# Scheda_motori_a4988.net
KiCad netlist of a schematic drawn in EAGLE
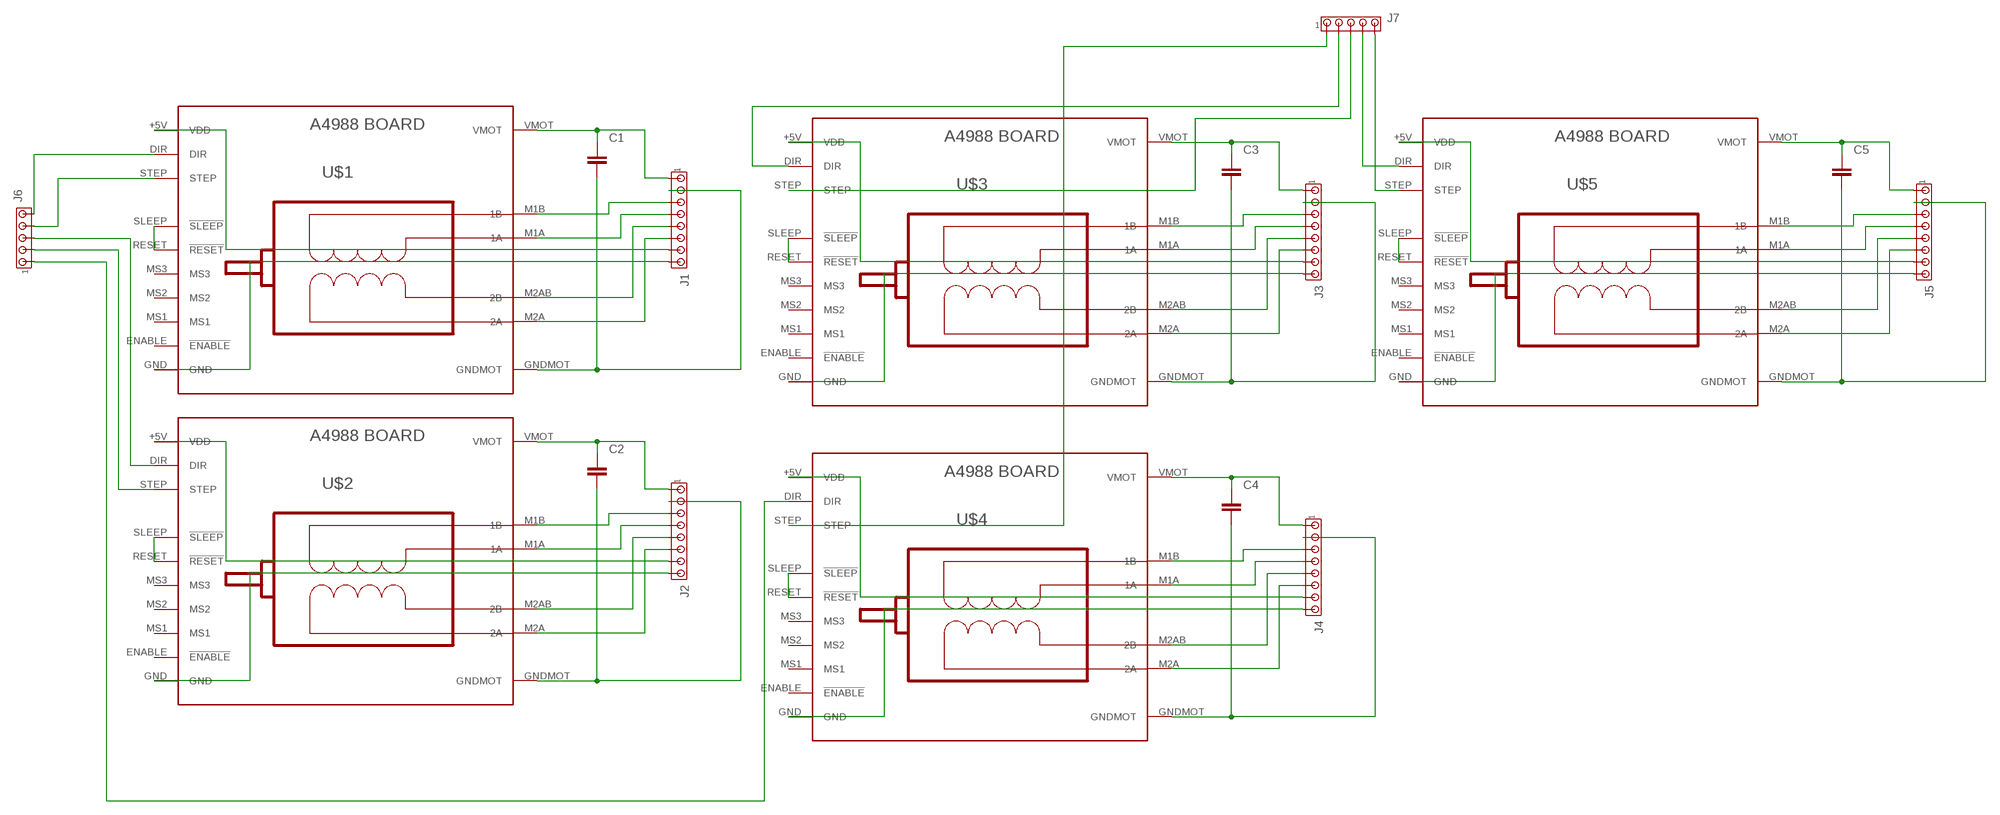
[diagram p0: schematic, sheet 1]

(export (version "E")
  (design (tool "Eeschema 10.0.6"))
  (components
    (comp (ref "C1")
      (value "C_RADIAL-12.5MM-DIA")
      (footprint "eagle-import:CAPRD550W60D1025H1250B")
      (libsource (lib "eagle-import") (part "CRADIAL-12.5MM-DIA_"))
    )
    (comp (ref "C2")
      (value "C_RADIAL-12.5MM-DIA")
      (footprint "eagle-import:CAPRD550W60D1025H1250B")
      (libsource (lib "eagle-import") (part "CRADIAL-12.5MM-DIA_"))
    )
    (comp (ref "C3")
      (value "C_RADIAL-12.5MM-DIA")
      (footprint "eagle-import:CAPRD550W60D1025H1250B")
      (libsource (lib "eagle-import") (part "CRADIAL-12.5MM-DIA_"))
    )
    (comp (ref "C4")
      (value "C_RADIAL-12.5MM-DIA")
      (footprint "eagle-import:CAPRD550W60D1025H1250B")
      (libsource (lib "eagle-import") (part "CRADIAL-12.5MM-DIA_"))
    )
    (comp (ref "C5")
      (value "C_RADIAL-12.5MM-DIA")
      (footprint "eagle-import:CAPRD550W60D1025H1250B")
      (libsource (lib "eagle-import") (part "CRADIAL-12.5MM-DIA_"))
    )
    (comp (ref "J1")
      (value "MTA08-100")
      (footprint "eagle-import:10X08MTA")
      (libsource (lib "eagle-import") (part "MTA08-100"))
    )
    (comp (ref "J2")
      (value "MTA08-100")
      (footprint "eagle-import:10X08MTA")
      (libsource (lib "eagle-import") (part "MTA08-100"))
    )
    (comp (ref "J3")
      (value "MTA08-100")
      (footprint "eagle-import:10X08MTA")
      (libsource (lib "eagle-import") (part "MTA08-100"))
    )
    (comp (ref "J4")
      (value "MTA08-100")
      (footprint "eagle-import:10X08MTA")
      (libsource (lib "eagle-import") (part "MTA08-100"))
    )
    (comp (ref "J5")
      (value "MTA08-100")
      (footprint "eagle-import:10X08MTA")
      (libsource (lib "eagle-import") (part "MTA08-100"))
    )
    (comp (ref "J6")
      (value "MTA05-156")
      (footprint "eagle-import:1X5MTA")
      (libsource (lib "eagle-import") (part "MTA05-156"))
    )
    (comp (ref "J7")
      (value "MTA05-156")
      (footprint "eagle-import:1X5MTA")
      (libsource (lib "eagle-import") (part "MTA05-156"))
    )
    (comp (ref "U$1")
      (value "BOARD_A4988")
      (footprint "eagle-import:BOARD_A4988")
      (libsource (lib "eagle-import") (part "BOARD_A4988"))
    )
    (comp (ref "U$2")
      (value "BOARD_A4988")
      (footprint "eagle-import:BOARD_A4988")
      (libsource (lib "eagle-import") (part "BOARD_A4988"))
    )
    (comp (ref "U$3")
      (value "BOARD_A4988")
      (footprint "eagle-import:BOARD_A4988")
      (libsource (lib "eagle-import") (part "BOARD_A4988"))
    )
    (comp (ref "U$4")
      (value "BOARD_A4988")
      (footprint "eagle-import:BOARD_A4988")
      (libsource (lib "eagle-import") (part "BOARD_A4988"))
    )
    (comp (ref "U$5")
      (value "BOARD_A4988")
      (footprint "eagle-import:BOARD_A4988")
      (libsource (lib "eagle-import") (part "BOARD_A4988"))
    )
  )
  (nets
    (net (code "1") (name "Net-(C1-Pad1)") (class "Default")
      (node (ref "C1") (pin "1") (pinfunction "1_1") (pintype "passive"))
      (node (ref "J1") (pin "1") (pinfunction "1_1") (pintype "passive"))
      (node (ref "U$1") (pin "VMOT") (pinfunction "VMOT_VMOT") (pintype "power_in"))
    )
    (net (code "2") (name "Net-(C1-Pad2)") (class "Default")
      (node (ref "C1") (pin "2") (pinfunction "2_2") (pintype "passive"))
      (node (ref "J1") (pin "2") (pinfunction "2_2") (pintype "passive"))
      (node (ref "U$1") (pin "GNDMOT") (pinfunction "GNDMOT_GNDMOT") (pintype "power_in"))
    )
    (net (code "3") (name "Net-(C2-Pad1)") (class "Default")
      (node (ref "C2") (pin "1") (pinfunction "1_1") (pintype "passive"))
      (node (ref "J2") (pin "1") (pinfunction "1_1") (pintype "passive"))
      (node (ref "U$2") (pin "VMOT") (pinfunction "VMOT_VMOT") (pintype "power_in"))
    )
    (net (code "4") (name "Net-(C2-Pad2)") (class "Default")
      (node (ref "C2") (pin "2") (pinfunction "2_2") (pintype "passive"))
      (node (ref "J2") (pin "2") (pinfunction "2_2") (pintype "passive"))
      (node (ref "U$2") (pin "GNDMOT") (pinfunction "GNDMOT_GNDMOT") (pintype "power_in"))
    )
    (net (code "5") (name "Net-(C3-Pad1)") (class "Default")
      (node (ref "C3") (pin "1") (pinfunction "1_1") (pintype "passive"))
      (node (ref "J3") (pin "1") (pinfunction "1_1") (pintype "passive"))
      (node (ref "U$3") (pin "VMOT") (pinfunction "VMOT_VMOT") (pintype "power_in"))
    )
    (net (code "6") (name "Net-(C3-Pad2)") (class "Default")
      (node (ref "C3") (pin "2") (pinfunction "2_2") (pintype "passive"))
      (node (ref "J3") (pin "2") (pinfunction "2_2") (pintype "passive"))
      (node (ref "U$3") (pin "GNDMOT") (pinfunction "GNDMOT_GNDMOT") (pintype "power_in"))
    )
    (net (code "7") (name "Net-(C4-Pad1)") (class "Default")
      (node (ref "C4") (pin "1") (pinfunction "1_1") (pintype "passive"))
      (node (ref "J4") (pin "1") (pinfunction "1_1") (pintype "passive"))
      (node (ref "U$4") (pin "VMOT") (pinfunction "VMOT_VMOT") (pintype "power_in"))
    )
    (net (code "8") (name "Net-(C4-Pad2)") (class "Default")
      (node (ref "C4") (pin "2") (pinfunction "2_2") (pintype "passive"))
      (node (ref "J4") (pin "2") (pinfunction "2_2") (pintype "passive"))
      (node (ref "U$4") (pin "GNDMOT") (pinfunction "GNDMOT_GNDMOT") (pintype "power_in"))
    )
    (net (code "9") (name "Net-(C5-Pad1)") (class "Default")
      (node (ref "C5") (pin "1") (pinfunction "1_1") (pintype "passive"))
      (node (ref "J5") (pin "1") (pinfunction "1_1") (pintype "passive"))
      (node (ref "U$5") (pin "VMOT") (pinfunction "VMOT_VMOT") (pintype "power_in"))
    )
    (net (code "10") (name "Net-(C5-Pad2)") (class "Default")
      (node (ref "C5") (pin "2") (pinfunction "2_2") (pintype "passive"))
      (node (ref "J5") (pin "2") (pinfunction "2_2") (pintype "passive"))
      (node (ref "U$5") (pin "GNDMOT") (pinfunction "GNDMOT_GNDMOT") (pintype "power_in"))
    )
    (net (code "11") (name "Net-(J1-Pad8)") (class "Default")
      (node (ref "J1") (pin "8") (pinfunction "8_8") (pintype "passive"))
      (node (ref "U$1") (pin "GND") (pinfunction "GND_GND") (pintype "power_in"))
    )
    (net (code "12") (name "Net-(J2-Pad8)") (class "Default")
      (node (ref "J2") (pin "8") (pinfunction "8_8") (pintype "passive"))
      (node (ref "U$2") (pin "GND") (pinfunction "GND_GND") (pintype "power_in"))
    )
    (net (code "13") (name "Net-(J3-Pad8)") (class "Default")
      (node (ref "J3") (pin "8") (pinfunction "8_8") (pintype "passive"))
      (node (ref "U$3") (pin "GND") (pinfunction "GND_GND") (pintype "power_in"))
    )
    (net (code "14") (name "Net-(J4-Pad8)") (class "Default")
      (node (ref "J4") (pin "8") (pinfunction "8_8") (pintype "passive"))
      (node (ref "U$4") (pin "GND") (pinfunction "GND_GND") (pintype "power_in"))
    )
    (net (code "15") (name "Net-(J5-Pad8)") (class "Default")
      (node (ref "J5") (pin "8") (pinfunction "8_8") (pintype "passive"))
      (node (ref "U$5") (pin "GND") (pinfunction "GND_GND") (pintype "power_in"))
    )
    (net (code "16") (name "Net-(J6-Pad1)") (class "Default")
      (node (ref "J6") (pin "1") (pinfunction "1_1") (pintype "passive"))
      (node (ref "U$4") (pin "DIR") (pinfunction "DIR_DIR") (pintype "input"))
    )
    (net (code "17") (name "Net-(J6-Pad2)") (class "Default")
      (node (ref "J6") (pin "2") (pinfunction "2_2") (pintype "passive"))
      (node (ref "U$2") (pin "STEP") (pinfunction "STEP_STEP") (pintype "input"))
    )
    (net (code "18") (name "Net-(J6-Pad3)") (class "Default")
      (node (ref "J6") (pin "3") (pinfunction "3_3") (pintype "passive"))
      (node (ref "U$2") (pin "DIR") (pinfunction "DIR_DIR") (pintype "input"))
    )
    (net (code "19") (name "Net-(J6-Pad4)") (class "Default")
      (node (ref "J6") (pin "4") (pinfunction "4_4") (pintype "passive"))
      (node (ref "U$1") (pin "STEP") (pinfunction "STEP_STEP") (pintype "input"))
    )
    (net (code "20") (name "Net-(J6-Pad5)") (class "Default")
      (node (ref "J6") (pin "5") (pinfunction "5_5") (pintype "passive"))
      (node (ref "U$1") (pin "DIR") (pinfunction "DIR_DIR") (pintype "input"))
    )
    (net (code "21") (name "Net-(J7-Pad1)") (class "Default")
      (node (ref "J7") (pin "1") (pinfunction "1_1") (pintype "passive"))
      (node (ref "U$4") (pin "STEP") (pinfunction "STEP_STEP") (pintype "input"))
    )
    (net (code "22") (name "Net-(J7-Pad2)") (class "Default")
      (node (ref "J7") (pin "2") (pinfunction "2_2") (pintype "passive"))
      (node (ref "U$3") (pin "DIR") (pinfunction "DIR_DIR") (pintype "input"))
    )
    (net (code "23") (name "Net-(J7-Pad3)") (class "Default")
      (node (ref "J7") (pin "3") (pinfunction "3_3") (pintype "passive"))
      (node (ref "U$3") (pin "STEP") (pinfunction "STEP_STEP") (pintype "input"))
    )
    (net (code "24") (name "Net-(J7-Pad4)") (class "Default")
      (node (ref "J7") (pin "4") (pinfunction "4_4") (pintype "passive"))
      (node (ref "U$5") (pin "DIR") (pinfunction "DIR_DIR") (pintype "input"))
    )
    (net (code "25") (name "Net-(J7-Pad5)") (class "Default")
      (node (ref "J7") (pin "5") (pinfunction "5_5") (pintype "passive"))
      (node (ref "U$5") (pin "STEP") (pinfunction "STEP_STEP") (pintype "input"))
    )
    (net (code "26") (name "Net-(U$1-1A)") (class "Default")
      (node (ref "J1") (pin "4") (pinfunction "4_4") (pintype "passive"))
      (node (ref "U$1") (pin "M1A") (pinfunction "1A_M1A") (pintype "output"))
    )
    (net (code "27") (name "Net-(U$1-1B)") (class "Default")
      (node (ref "J1") (pin "3") (pinfunction "3_3") (pintype "passive"))
      (node (ref "U$1") (pin "M1B") (pinfunction "1B_M1B") (pintype "output"))
    )
    (net (code "28") (name "Net-(U$1-2A)") (class "Default")
      (node (ref "J1") (pin "6") (pinfunction "6_6") (pintype "passive"))
      (node (ref "U$1") (pin "M2A") (pinfunction "2A_M2A") (pintype "output"))
    )
    (net (code "29") (name "Net-(U$1-2B)") (class "Default")
      (node (ref "J1") (pin "5") (pinfunction "5_5") (pintype "passive"))
      (node (ref "U$1") (pin "M2AB") (pinfunction "2B_M2AB") (pintype "output"))
    )
    (net (code "30") (name "Net-(U$1-VDD)") (class "Default")
      (node (ref "J1") (pin "7") (pinfunction "7_7") (pintype "passive"))
      (node (ref "U$1") (pin "+5V") (pinfunction "VDD_+5V") (pintype "power_in"))
    )
    (net (code "31") (name "Net-(U$1-~{RESET})") (class "Default")
      (node (ref "U$1") (pin "RESET") (pinfunction "~{RESET}_RESET") (pintype "input"))
      (node (ref "U$1") (pin "SLEEP") (pinfunction "~{SLEEP}_SLEEP") (pintype "input"))
    )
    (net (code "32") (name "Net-(U$2-1A)") (class "Default")
      (node (ref "J2") (pin "4") (pinfunction "4_4") (pintype "passive"))
      (node (ref "U$2") (pin "M1A") (pinfunction "1A_M1A") (pintype "output"))
    )
    (net (code "33") (name "Net-(U$2-1B)") (class "Default")
      (node (ref "J2") (pin "3") (pinfunction "3_3") (pintype "passive"))
      (node (ref "U$2") (pin "M1B") (pinfunction "1B_M1B") (pintype "output"))
    )
    (net (code "34") (name "Net-(U$2-2A)") (class "Default")
      (node (ref "J2") (pin "6") (pinfunction "6_6") (pintype "passive"))
      (node (ref "U$2") (pin "M2A") (pinfunction "2A_M2A") (pintype "output"))
    )
    (net (code "35") (name "Net-(U$2-2B)") (class "Default")
      (node (ref "J2") (pin "5") (pinfunction "5_5") (pintype "passive"))
      (node (ref "U$2") (pin "M2AB") (pinfunction "2B_M2AB") (pintype "output"))
    )
    (net (code "36") (name "Net-(U$2-VDD)") (class "Default")
      (node (ref "J2") (pin "7") (pinfunction "7_7") (pintype "passive"))
      (node (ref "U$2") (pin "+5V") (pinfunction "VDD_+5V") (pintype "power_in"))
    )
    (net (code "37") (name "Net-(U$2-~{RESET})") (class "Default")
      (node (ref "U$2") (pin "RESET") (pinfunction "~{RESET}_RESET") (pintype "input"))
      (node (ref "U$2") (pin "SLEEP") (pinfunction "~{SLEEP}_SLEEP") (pintype "input"))
    )
    (net (code "38") (name "Net-(U$3-1A)") (class "Default")
      (node (ref "J3") (pin "4") (pinfunction "4_4") (pintype "passive"))
      (node (ref "U$3") (pin "M1A") (pinfunction "1A_M1A") (pintype "output"))
    )
    (net (code "39") (name "Net-(U$3-1B)") (class "Default")
      (node (ref "J3") (pin "3") (pinfunction "3_3") (pintype "passive"))
      (node (ref "U$3") (pin "M1B") (pinfunction "1B_M1B") (pintype "output"))
    )
    (net (code "40") (name "Net-(U$3-2A)") (class "Default")
      (node (ref "J3") (pin "6") (pinfunction "6_6") (pintype "passive"))
      (node (ref "U$3") (pin "M2A") (pinfunction "2A_M2A") (pintype "output"))
    )
    (net (code "41") (name "Net-(U$3-2B)") (class "Default")
      (node (ref "J3") (pin "5") (pinfunction "5_5") (pintype "passive"))
      (node (ref "U$3") (pin "M2AB") (pinfunction "2B_M2AB") (pintype "output"))
    )
    (net (code "42") (name "Net-(U$3-VDD)") (class "Default")
      (node (ref "J3") (pin "7") (pinfunction "7_7") (pintype "passive"))
      (node (ref "U$3") (pin "+5V") (pinfunction "VDD_+5V") (pintype "power_in"))
    )
    (net (code "43") (name "Net-(U$3-~{RESET})") (class "Default")
      (node (ref "U$3") (pin "RESET") (pinfunction "~{RESET}_RESET") (pintype "input"))
      (node (ref "U$3") (pin "SLEEP") (pinfunction "~{SLEEP}_SLEEP") (pintype "input"))
    )
    (net (code "44") (name "Net-(U$4-1A)") (class "Default")
      (node (ref "J4") (pin "4") (pinfunction "4_4") (pintype "passive"))
      (node (ref "U$4") (pin "M1A") (pinfunction "1A_M1A") (pintype "output"))
    )
    (net (code "45") (name "Net-(U$4-1B)") (class "Default")
      (node (ref "J4") (pin "3") (pinfunction "3_3") (pintype "passive"))
      (node (ref "U$4") (pin "M1B") (pinfunction "1B_M1B") (pintype "output"))
    )
    (net (code "46") (name "Net-(U$4-2A)") (class "Default")
      (node (ref "J4") (pin "6") (pinfunction "6_6") (pintype "passive"))
      (node (ref "U$4") (pin "M2A") (pinfunction "2A_M2A") (pintype "output"))
    )
    (net (code "47") (name "Net-(U$4-2B)") (class "Default")
      (node (ref "J4") (pin "5") (pinfunction "5_5") (pintype "passive"))
      (node (ref "U$4") (pin "M2AB") (pinfunction "2B_M2AB") (pintype "output"))
    )
    (net (code "48") (name "Net-(U$4-VDD)") (class "Default")
      (node (ref "J4") (pin "7") (pinfunction "7_7") (pintype "passive"))
      (node (ref "U$4") (pin "+5V") (pinfunction "VDD_+5V") (pintype "power_in"))
    )
    (net (code "49") (name "Net-(U$4-~{RESET})") (class "Default")
      (node (ref "U$4") (pin "RESET") (pinfunction "~{RESET}_RESET") (pintype "input"))
      (node (ref "U$4") (pin "SLEEP") (pinfunction "~{SLEEP}_SLEEP") (pintype "input"))
    )
    (net (code "50") (name "Net-(U$5-1A)") (class "Default")
      (node (ref "J5") (pin "4") (pinfunction "4_4") (pintype "passive"))
      (node (ref "U$5") (pin "M1A") (pinfunction "1A_M1A") (pintype "output"))
    )
    (net (code "51") (name "Net-(U$5-1B)") (class "Default")
      (node (ref "J5") (pin "3") (pinfunction "3_3") (pintype "passive"))
      (node (ref "U$5") (pin "M1B") (pinfunction "1B_M1B") (pintype "output"))
    )
    (net (code "52") (name "Net-(U$5-2A)") (class "Default")
      (node (ref "J5") (pin "6") (pinfunction "6_6") (pintype "passive"))
      (node (ref "U$5") (pin "M2A") (pinfunction "2A_M2A") (pintype "output"))
    )
    (net (code "53") (name "Net-(U$5-2B)") (class "Default")
      (node (ref "J5") (pin "5") (pinfunction "5_5") (pintype "passive"))
      (node (ref "U$5") (pin "M2AB") (pinfunction "2B_M2AB") (pintype "output"))
    )
    (net (code "54") (name "Net-(U$5-VDD)") (class "Default")
      (node (ref "J5") (pin "7") (pinfunction "7_7") (pintype "passive"))
      (node (ref "U$5") (pin "+5V") (pinfunction "VDD_+5V") (pintype "power_in"))
    )
    (net (code "55") (name "Net-(U$5-~{RESET})") (class "Default")
      (node (ref "U$5") (pin "RESET") (pinfunction "~{RESET}_RESET") (pintype "input"))
      (node (ref "U$5") (pin "SLEEP") (pinfunction "~{SLEEP}_SLEEP") (pintype "input"))
    )
    (net (code "56") (name "unconnected-(U$1-PadMS1)") (class "Default")
      (node (ref "U$1") (pin "MS1") (pinfunction "MS1_MS1") (pintype "input"))
    )
    (net (code "57") (name "unconnected-(U$1-PadMS2)") (class "Default")
      (node (ref "U$1") (pin "MS2") (pinfunction "MS2_MS2") (pintype "input"))
    )
    (net (code "58") (name "unconnected-(U$1-PadMS3)") (class "Default")
      (node (ref "U$1") (pin "MS3") (pinfunction "MS3_MS3") (pintype "input"))
    )
    (net (code "59") (name "unconnected-(U$1-~{ENABLE}-PadENABLE)") (class "Default")
      (node (ref "U$1") (pin "ENABLE") (pinfunction "~{ENABLE}_ENABLE") (pintype "input"))
    )
    (net (code "60") (name "unconnected-(U$2-PadMS1)") (class "Default")
      (node (ref "U$2") (pin "MS1") (pinfunction "MS1_MS1") (pintype "input"))
    )
    (net (code "61") (name "unconnected-(U$2-PadMS2)") (class "Default")
      (node (ref "U$2") (pin "MS2") (pinfunction "MS2_MS2") (pintype "input"))
    )
    (net (code "62") (name "unconnected-(U$2-PadMS3)") (class "Default")
      (node (ref "U$2") (pin "MS3") (pinfunction "MS3_MS3") (pintype "input"))
    )
    (net (code "63") (name "unconnected-(U$2-~{ENABLE}-PadENABLE)") (class "Default")
      (node (ref "U$2") (pin "ENABLE") (pinfunction "~{ENABLE}_ENABLE") (pintype "input"))
    )
    (net (code "64") (name "unconnected-(U$3-PadMS1)") (class "Default")
      (node (ref "U$3") (pin "MS1") (pinfunction "MS1_MS1") (pintype "input"))
    )
    (net (code "65") (name "unconnected-(U$3-PadMS2)") (class "Default")
      (node (ref "U$3") (pin "MS2") (pinfunction "MS2_MS2") (pintype "input"))
    )
    (net (code "66") (name "unconnected-(U$3-PadMS3)") (class "Default")
      (node (ref "U$3") (pin "MS3") (pinfunction "MS3_MS3") (pintype "input"))
    )
    (net (code "67") (name "unconnected-(U$3-~{ENABLE}-PadENABLE)") (class "Default")
      (node (ref "U$3") (pin "ENABLE") (pinfunction "~{ENABLE}_ENABLE") (pintype "input"))
    )
    (net (code "68") (name "unconnected-(U$4-PadMS1)") (class "Default")
      (node (ref "U$4") (pin "MS1") (pinfunction "MS1_MS1") (pintype "input"))
    )
    (net (code "69") (name "unconnected-(U$4-PadMS2)") (class "Default")
      (node (ref "U$4") (pin "MS2") (pinfunction "MS2_MS2") (pintype "input"))
    )
    (net (code "70") (name "unconnected-(U$4-PadMS3)") (class "Default")
      (node (ref "U$4") (pin "MS3") (pinfunction "MS3_MS3") (pintype "input"))
    )
    (net (code "71") (name "unconnected-(U$4-~{ENABLE}-PadENABLE)") (class "Default")
      (node (ref "U$4") (pin "ENABLE") (pinfunction "~{ENABLE}_ENABLE") (pintype "input"))
    )
    (net (code "72") (name "unconnected-(U$5-PadMS1)") (class "Default")
      (node (ref "U$5") (pin "MS1") (pinfunction "MS1_MS1") (pintype "input"))
    )
    (net (code "73") (name "unconnected-(U$5-PadMS2)") (class "Default")
      (node (ref "U$5") (pin "MS2") (pinfunction "MS2_MS2") (pintype "input"))
    )
    (net (code "74") (name "unconnected-(U$5-PadMS3)") (class "Default")
      (node (ref "U$5") (pin "MS3") (pinfunction "MS3_MS3") (pintype "input"))
    )
    (net (code "75") (name "unconnected-(U$5-~{ENABLE}-PadENABLE)") (class "Default")
      (node (ref "U$5") (pin "ENABLE") (pinfunction "~{ENABLE}_ENABLE") (pintype "input"))
    )
  )
)
